# EV76C661_Motherboard.net
KiCad netlist of a schematic drawn in Altium Designer
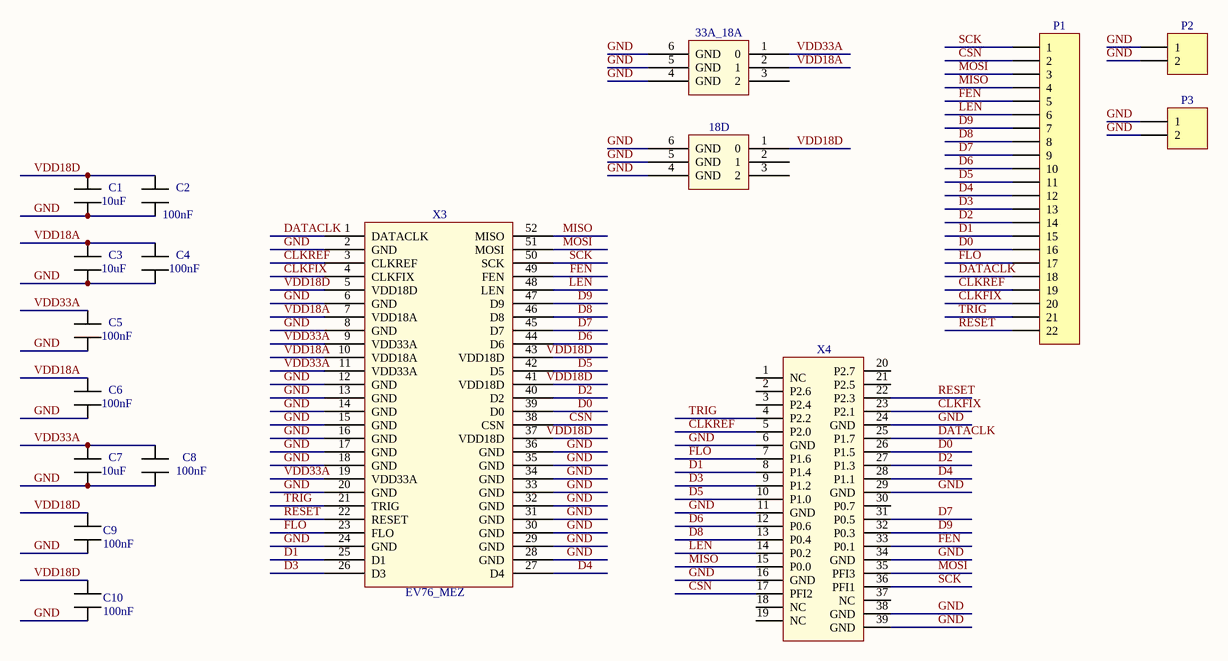
[diagram p0: EV76C661_Motherboard.SchDoc]

(export (version "E")
  (design (tool "Eeschema 10.0.6"))
  (components
    (comp (ref "18D") (value "POWER") (footprint "POWER") (libsource (lib "aab_Schlib") (part "POWER")))
    (comp (ref "33A_18A") (value "POWER") (footprint "POWER") (libsource (lib "aab_Schlib") (part "POWER")))
    (comp (ref "C1") (value "10uF") (footprint "Cap_BIG") (libsource (lib "aab_Schlib") (part "CAP_BIG")))
    (comp (ref "C2")
      (value "100nF")
      (footprint "aab_Passive:CAP_SMALL")
      (libsource (lib "aab_Schlib") (part "CAP_SMALL"))
    )
    (comp (ref "C3") (value "10uF") (footprint "Cap_BIG") (libsource (lib "aab_Schlib") (part "CAP_BIG")))
    (comp (ref "C4")
      (value "100nF")
      (footprint "aab_Passive:CAP_SMALL")
      (libsource (lib "aab_Schlib") (part "CAP_SMALL"))
    )
    (comp (ref "C5")
      (value "100nF")
      (footprint "aab_Passive:CAP_SMALL")
      (libsource (lib "aab_Schlib") (part "CAP_SMALL"))
    )
    (comp (ref "C6")
      (value "100nF")
      (footprint "CAP_SMALL")
      (libsource (lib "aab_Schlib") (part "CAP_SMALL"))
    )
    (comp (ref "C7") (value "10uF") (footprint "Cap_BIG") (libsource (lib "aab_Schlib") (part "CAP_BIG")))
    (comp (ref "C8")
      (value "100nF")
      (footprint "CAP_SMALL")
      (libsource (lib "aab_Schlib") (part "CAP_SMALL"))
    )
    (comp (ref "C9")
      (value "100nF")
      (footprint "aab_Passive:CAP_SMALL")
      (libsource (lib "aab_Schlib") (part "CAP_SMALL"))
    )
    (comp (ref "C10")
      (value "100nF")
      (footprint "aab_Passive:CAP_SMALL")
      (libsource (lib "aab_Schlib") (part "CAP_SMALL"))
    )
    (comp (ref "P1")
      (value "Header 22")
      (footprint "HDR1X22")
      (description "Header, 22-Pin")
      (fields (field (name "PUBLISHER") "Altium Limited"))
      (libsource (lib "Miscellaneous Connectors") (part "Header 22"))
    )
    (comp (ref "P2")
      (value "Header 2")
      (footprint "HDR1X2")
      (description "Header, 2-Pin")
      (fields (field (name "PUBLISHER") "Altium Limited"))
      (libsource (lib "Miscellaneous Connectors") (part "Header 2"))
    )
    (comp (ref "P3")
      (value "Header 2")
      (footprint "HDR1X2")
      (description "Header, 2-Pin")
      (fields (field (name "PUBLISHER") "Altium Limited"))
      (libsource (lib "Miscellaneous Connectors") (part "Header 2"))
    )
    (comp (ref "X3")
      (value "EV76_MEZ")
      (footprint "EV76C661_MEZONINE")
      (libsource (lib "aab_Schlib") (part "EV76C661_MEZ"))
    )
    (comp (ref "X4")
      (value "CHEAP_CON_37_FEMALE")
      (footprint "CHEAP_CONN_FEMALE")
      (libsource (lib "aab_Schlib") (part "CHEAP_CON_37_FEMALE"))
    )
  )
  (nets
    (net (code "1") (name "/CLKFIX") (class "Default")
      (node (ref "P1") (pin "20") (pinfunction "20_20") (pintype "passive"))
      (node (ref "X3") (pin "4") (pinfunction "CLKFIX_4") (pintype "passive"))
      (node (ref "X4") (pin "23") (pinfunction "P2.1_23") (pintype "passive"))
    )
    (net (code "2") (name "/CLKREF") (class "Default")
      (node (ref "P1") (pin "19") (pinfunction "19_19") (pintype "passive"))
      (node (ref "X3") (pin "3") (pinfunction "CLKREF_3") (pintype "passive"))
      (node (ref "X4") (pin "5") (pinfunction "P2.0_5") (pintype "passive"))
    )
    (net (code "3") (name "/CSN") (class "Default")
      (node (ref "P1") (pin "2") (pinfunction "2_2") (pintype "passive"))
      (node (ref "X3") (pin "38") (pinfunction "CSN_38") (pintype "passive"))
      (node (ref "X4") (pin "17") (pinfunction "PFI2_17") (pintype "passive"))
    )
    (net (code "4") (name "/D0") (class "Default")
      (node (ref "P1") (pin "16") (pinfunction "16_16") (pintype "passive"))
      (node (ref "X3") (pin "39") (pinfunction "D0_39") (pintype "passive"))
      (node (ref "X4") (pin "26") (pinfunction "P1.5_26") (pintype "passive"))
    )
    (net (code "5") (name "/D1") (class "Default")
      (node (ref "P1") (pin "15") (pinfunction "15_15") (pintype "passive"))
      (node (ref "X3") (pin "25") (pinfunction "D1_25") (pintype "passive"))
      (node (ref "X4") (pin "8") (pinfunction "P1.4_8") (pintype "passive"))
    )
    (net (code "6") (name "/D2") (class "Default")
      (node (ref "P1") (pin "14") (pinfunction "14_14") (pintype "passive"))
      (node (ref "X3") (pin "40") (pinfunction "D2_40") (pintype "passive"))
      (node (ref "X4") (pin "27") (pinfunction "P1.3_27") (pintype "passive"))
    )
    (net (code "7") (name "/D3") (class "Default")
      (node (ref "P1") (pin "13") (pinfunction "13_13") (pintype "passive"))
      (node (ref "X3") (pin "26") (pinfunction "D3_26") (pintype "passive"))
      (node (ref "X4") (pin "9") (pinfunction "P1.2_9") (pintype "passive"))
    )
    (net (code "8") (name "/D4") (class "Default")
      (node (ref "P1") (pin "12") (pinfunction "12_12") (pintype "passive"))
      (node (ref "X3") (pin "27") (pinfunction "D4_27") (pintype "passive"))
      (node (ref "X4") (pin "28") (pinfunction "P1.1_28") (pintype "passive"))
    )
    (net (code "9") (name "/D5") (class "Default")
      (node (ref "P1") (pin "11") (pinfunction "11_11") (pintype "passive"))
      (node (ref "X3") (pin "42") (pinfunction "D5_42") (pintype "passive"))
      (node (ref "X4") (pin "10") (pinfunction "P1.0_10") (pintype "passive"))
    )
    (net (code "10") (name "/D6") (class "Default")
      (node (ref "P1") (pin "10") (pinfunction "10_10") (pintype "passive"))
      (node (ref "X3") (pin "44") (pinfunction "D6_44") (pintype "passive"))
      (node (ref "X4") (pin "12") (pinfunction "P0.6_12") (pintype "passive"))
    )
    (net (code "11") (name "/D7") (class "Default")
      (node (ref "P1") (pin "9") (pinfunction "9_9") (pintype "passive"))
      (node (ref "X3") (pin "45") (pinfunction "D7_45") (pintype "passive"))
      (node (ref "X4") (pin "31") (pinfunction "P0.5_31") (pintype "passive"))
    )
    (net (code "12") (name "/D8") (class "Default")
      (node (ref "P1") (pin "8") (pinfunction "8_8") (pintype "passive"))
      (node (ref "X3") (pin "46") (pinfunction "D8_46") (pintype "passive"))
      (node (ref "X4") (pin "13") (pinfunction "P0.4_13") (pintype "passive"))
    )
    (net (code "13") (name "/D9") (class "Default")
      (node (ref "P1") (pin "7") (pinfunction "7_7") (pintype "passive"))
      (node (ref "X3") (pin "47") (pinfunction "D9_47") (pintype "passive"))
      (node (ref "X4") (pin "32") (pinfunction "P0.3_32") (pintype "passive"))
    )
    (net (code "14") (name "/DATACLK") (class "Default")
      (node (ref "P1") (pin "18") (pinfunction "18_18") (pintype "passive"))
      (node (ref "X3") (pin "1") (pinfunction "DATACLK_1") (pintype "passive"))
      (node (ref "X4") (pin "25") (pinfunction "P1.7_25") (pintype "passive"))
    )
    (net (code "15") (name "/FEN") (class "Default")
      (node (ref "P1") (pin "5") (pinfunction "5_5") (pintype "passive"))
      (node (ref "X3") (pin "49") (pinfunction "FEN_49") (pintype "passive"))
      (node (ref "X4") (pin "33") (pinfunction "P0.1_33") (pintype "passive"))
    )
    (net (code "16") (name "/FLO") (class "Default")
      (node (ref "P1") (pin "17") (pinfunction "17_17") (pintype "passive"))
      (node (ref "X3") (pin "23") (pinfunction "FLO_23") (pintype "passive"))
      (node (ref "X4") (pin "7") (pinfunction "P1.6_7") (pintype "passive"))
    )
    (net (code "17") (name "/GND") (class "Default")
      (node (ref "18D") (pin "4") (pinfunction "GND_4") (pintype "passive"))
      (node (ref "18D") (pin "5") (pinfunction "GND_5") (pintype "passive"))
      (node (ref "18D") (pin "6") (pinfunction "GND_6") (pintype "passive"))
      (node (ref "33A_18A") (pin "4") (pinfunction "GND_4") (pintype "passive"))
      (node (ref "33A_18A") (pin "5") (pinfunction "GND_5") (pintype "passive"))
      (node (ref "33A_18A") (pin "6") (pinfunction "GND_6") (pintype "passive"))
      (node (ref "C1") (pin "1") (pinfunction "1_1") (pintype "passive"))
      (node (ref "C10") (pin "1") (pinfunction "1_1") (pintype "passive"))
      (node (ref "C2") (pin "2") (pinfunction "2_2") (pintype "passive"))
      (node (ref "C3") (pin "1") (pinfunction "1_1") (pintype "passive"))
      (node (ref "C4") (pin "2") (pinfunction "2_2") (pintype "passive"))
      (node (ref "C5") (pin "1") (pinfunction "1_1") (pintype "passive"))
      (node (ref "C6") (pin "2") (pinfunction "2_2") (pintype "passive"))
      (node (ref "C7") (pin "1") (pinfunction "1_1") (pintype "passive"))
      (node (ref "C8") (pin "2") (pinfunction "2_2") (pintype "passive"))
      (node (ref "C9") (pin "1") (pinfunction "1_1") (pintype "passive"))
      (node (ref "P2") (pin "1") (pinfunction "1_1") (pintype "passive"))
      (node (ref "P2") (pin "2") (pinfunction "2_2") (pintype "passive"))
      (node (ref "P3") (pin "1") (pinfunction "1_1") (pintype "passive"))
      (node (ref "P3") (pin "2") (pinfunction "2_2") (pintype "passive"))
      (node (ref "X3") (pin "12") (pinfunction "GND_12") (pintype "passive"))
      (node (ref "X3") (pin "13") (pinfunction "GND_13") (pintype "passive"))
      (node (ref "X3") (pin "14") (pinfunction "GND_14") (pintype "passive"))
      (node (ref "X3") (pin "15") (pinfunction "GND_15") (pintype "passive"))
      (node (ref "X3") (pin "16") (pinfunction "GND_16") (pintype "passive"))
      (node (ref "X3") (pin "17") (pinfunction "GND_17") (pintype "passive"))
      (node (ref "X3") (pin "18") (pinfunction "GND_18") (pintype "passive"))
      (node (ref "X3") (pin "2") (pinfunction "GND_2") (pintype "passive"))
      (node (ref "X3") (pin "20") (pinfunction "GND_20") (pintype "passive"))
      (node (ref "X3") (pin "24") (pinfunction "GND_24") (pintype "passive"))
      (node (ref "X3") (pin "28") (pinfunction "GND_28") (pintype "passive"))
      (node (ref "X3") (pin "29") (pinfunction "GND_29") (pintype "passive"))
      (node (ref "X3") (pin "30") (pinfunction "GND_30") (pintype "passive"))
      (node (ref "X3") (pin "31") (pinfunction "GND_31") (pintype "passive"))
      (node (ref "X3") (pin "32") (pinfunction "GND_32") (pintype "passive"))
      (node (ref "X3") (pin "33") (pinfunction "GND_33") (pintype "passive"))
      (node (ref "X3") (pin "34") (pinfunction "GND_34") (pintype "passive"))
      (node (ref "X3") (pin "35") (pinfunction "GND_35") (pintype "passive"))
      (node (ref "X3") (pin "36") (pinfunction "GND_36") (pintype "passive"))
      (node (ref "X3") (pin "6") (pinfunction "GND_6") (pintype "passive"))
      (node (ref "X3") (pin "8") (pinfunction "GND_8") (pintype "passive"))
      (node (ref "X4") (pin "11") (pinfunction "GND_11") (pintype "passive"))
      (node (ref "X4") (pin "16") (pinfunction "GND_16") (pintype "passive"))
      (node (ref "X4") (pin "24") (pinfunction "GND_24") (pintype "passive"))
      (node (ref "X4") (pin "29") (pinfunction "GND_29") (pintype "passive"))
      (node (ref "X4") (pin "34") (pinfunction "GND_34") (pintype "passive"))
      (node (ref "X4") (pin "38") (pinfunction "GND_38") (pintype "passive"))
      (node (ref "X4") (pin "39") (pinfunction "GND_39") (pintype "passive"))
      (node (ref "X4") (pin "6") (pinfunction "GND_6") (pintype "passive"))
    )
    (net (code "18") (name "/LEN") (class "Default")
      (node (ref "P1") (pin "6") (pinfunction "6_6") (pintype "passive"))
      (node (ref "X3") (pin "48") (pinfunction "LEN_48") (pintype "passive"))
      (node (ref "X4") (pin "14") (pinfunction "P0.2_14") (pintype "passive"))
    )
    (net (code "19") (name "/MISO") (class "Default")
      (node (ref "P1") (pin "4") (pinfunction "4_4") (pintype "passive"))
      (node (ref "X3") (pin "52") (pinfunction "MISO_52") (pintype "passive"))
      (node (ref "X4") (pin "15") (pinfunction "P0.0_15") (pintype "passive"))
    )
    (net (code "20") (name "/MOSI") (class "Default")
      (node (ref "P1") (pin "3") (pinfunction "3_3") (pintype "passive"))
      (node (ref "X3") (pin "51") (pinfunction "MOSI_51") (pintype "passive"))
      (node (ref "X4") (pin "35") (pinfunction "PFI3_35") (pintype "passive"))
    )
    (net (code "21") (name "/RESET") (class "Default")
      (node (ref "P1") (pin "22") (pinfunction "22_22") (pintype "passive"))
      (node (ref "X3") (pin "22") (pinfunction "RESET_22") (pintype "passive"))
      (node (ref "X4") (pin "22") (pinfunction "P2.3_22") (pintype "passive"))
    )
    (net (code "22") (name "/SCK") (class "Default")
      (node (ref "P1") (pin "1") (pinfunction "1_1") (pintype "passive"))
      (node (ref "X3") (pin "50") (pinfunction "SCK_50") (pintype "passive"))
      (node (ref "X4") (pin "36") (pinfunction "PFI1_36") (pintype "passive"))
    )
    (net (code "23") (name "/TRIG") (class "Default")
      (node (ref "P1") (pin "21") (pinfunction "21_21") (pintype "passive"))
      (node (ref "X3") (pin "21") (pinfunction "TRIG_21") (pintype "passive"))
      (node (ref "X4") (pin "4") (pinfunction "P2.2_4") (pintype "passive"))
    )
    (net (code "24") (name "/VDD18A") (class "Default")
      (node (ref "33A_18A") (pin "2") (pinfunction "1_2") (pintype "passive"))
      (node (ref "C3") (pin "2") (pinfunction "2_2") (pintype "passive"))
      (node (ref "C4") (pin "1") (pinfunction "1_1") (pintype "passive"))
      (node (ref "C6") (pin "1") (pinfunction "1_1") (pintype "passive"))
      (node (ref "X3") (pin "10") (pinfunction "VDD18A_10") (pintype "passive"))
      (node (ref "X3") (pin "7") (pinfunction "VDD18A_7") (pintype "passive"))
    )
    (net (code "25") (name "/VDD18D") (class "Default")
      (node (ref "18D") (pin "1") (pinfunction "0_1") (pintype "passive"))
      (node (ref "C1") (pin "2") (pinfunction "2_2") (pintype "passive"))
      (node (ref "C10") (pin "2") (pinfunction "2_2") (pintype "passive"))
      (node (ref "C2") (pin "1") (pinfunction "1_1") (pintype "passive"))
      (node (ref "C9") (pin "2") (pinfunction "2_2") (pintype "passive"))
      (node (ref "X3") (pin "37") (pinfunction "VDD18D_37") (pintype "passive"))
      (node (ref "X3") (pin "41") (pinfunction "VDD18D_41") (pintype "passive"))
      (node (ref "X3") (pin "43") (pinfunction "VDD18D_43") (pintype "passive"))
      (node (ref "X3") (pin "5") (pinfunction "VDD18D_5") (pintype "passive"))
    )
    (net (code "26") (name "/VDD33A") (class "Default")
      (node (ref "33A_18A") (pin "1") (pinfunction "0_1") (pintype "passive"))
      (node (ref "C5") (pin "2") (pinfunction "2_2") (pintype "passive"))
      (node (ref "C7") (pin "2") (pinfunction "2_2") (pintype "passive"))
      (node (ref "C8") (pin "1") (pinfunction "1_1") (pintype "passive"))
      (node (ref "X3") (pin "11") (pinfunction "VDD33A_11") (pintype "passive"))
      (node (ref "X3") (pin "19") (pinfunction "VDD33A_19") (pintype "passive"))
      (node (ref "X3") (pin "9") (pinfunction "VDD33A_9") (pintype "passive"))
    )
    (net (code "27") (name "unconnected-(18D-1-Pad2)") (class "Default")
      (node (ref "18D") (pin "2") (pinfunction "1_2") (pintype "passive"))
    )
    (net (code "28") (name "unconnected-(18D-2-Pad3)") (class "Default")
      (node (ref "18D") (pin "3") (pinfunction "2_3") (pintype "passive"))
    )
    (net (code "29") (name "unconnected-(33A_18A-2-Pad3)") (class "Default")
      (node (ref "33A_18A") (pin "3") (pinfunction "2_3") (pintype "passive"))
    )
    (net (code "30") (name "unconnected-(X4-NC-Pad1)") (class "Default")
      (node (ref "X4") (pin "1") (pinfunction "NC_1") (pintype "passive"))
    )
    (net (code "31") (name "unconnected-(X4-NC-Pad18)") (class "Default")
      (node (ref "X4") (pin "18") (pinfunction "NC_18") (pintype "passive"))
    )
    (net (code "32") (name "unconnected-(X4-NC-Pad19)") (class "Default")
      (node (ref "X4") (pin "19") (pinfunction "NC_19") (pintype "passive"))
    )
    (net (code "33") (name "unconnected-(X4-NC-Pad37)") (class "Default")
      (node (ref "X4") (pin "37") (pinfunction "NC_37") (pintype "passive"))
    )
    (net (code "34") (name "unconnected-(X4-P0.7-Pad30)") (class "Default")
      (node (ref "X4") (pin "30") (pinfunction "P0.7_30") (pintype "passive"))
    )
    (net (code "35") (name "unconnected-(X4-P2.4-Pad3)") (class "Default")
      (node (ref "X4") (pin "3") (pinfunction "P2.4_3") (pintype "passive"))
    )
    (net (code "36") (name "unconnected-(X4-P2.5-Pad21)") (class "Default")
      (node (ref "X4") (pin "21") (pinfunction "P2.5_21") (pintype "passive"))
    )
    (net (code "37") (name "unconnected-(X4-P2.6-Pad2)") (class "Default")
      (node (ref "X4") (pin "2") (pinfunction "P2.6_2") (pintype "passive"))
    )
    (net (code "38") (name "unconnected-(X4-P2.7-Pad20)") (class "Default")
      (node (ref "X4") (pin "20") (pinfunction "P2.7_20") (pintype "passive"))
    )
  )
)
